# OperacionesLogicasSchmatic.net
KiCad netlist of a schematic drawn in Altium Designer
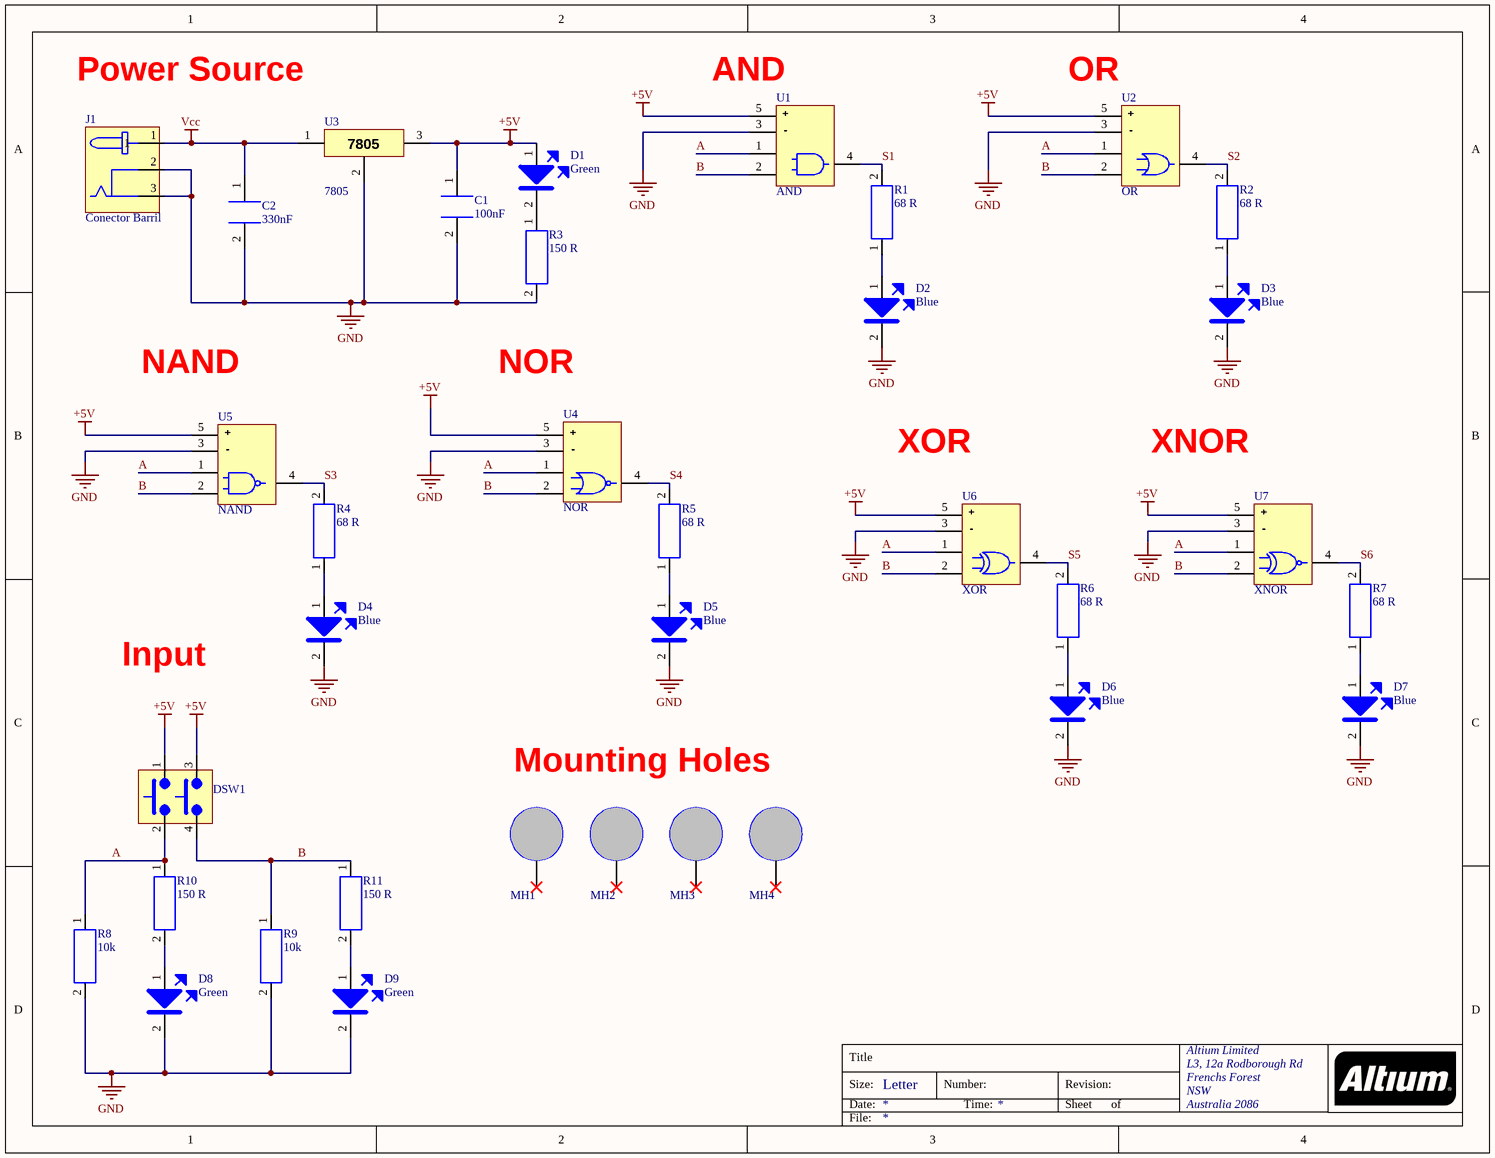
[diagram p0: OperacionesLogicasSchmatic.SchDoc]

(export (version "E")
  (design (tool "Eeschema 10.0.6"))
  (components
    (comp (ref "C1")
      (value "100nF")
      (footprint "Capacitor0805")
      (fields
        (field (name "MANUFACTURER") "KEMET")
        (field (name "MANUFACTURER PART NUMBER") "C0805C104K4RACTU")
        (field (name "TOLERANCE") "10%")
      )
      (libsource (lib "Operaciones_SCH_LIBRARY") (part "C0805C104K4RACTU"))
    )
    (comp (ref "C2")
      (value "330nF")
      (footprint "Capacitor0805")
      (description "CAP CER 0.33UF 16V X7R 0805")
      (fields
        (field (name "MANUFACTURER") "Yageo")
        (field (name "MANUFACTURER PART NUMBER") "CC0805JKX7R7BB334")
      )
      (libsource (lib "Operaciones_SCH_LIBRARY") (part "CC0805JKX7R7BB334"))
    )
    (comp (ref "D1")
      (value "Green")
      (footprint "Led0603")
      (description "LED GREEN CLEAR 0603 SMD")
      (fields
        (field (name "MANUFACTURER") "Vishay Lite-On")
        (field (name "MANUFACTURER PART NUMBER") "LTST-C191GKT")
      )
      (libsource (lib "Operaciones_SCH_LIBRARY") (part "LTST-C191GKT"))
    )
    (comp (ref "D2")
      (value "Blue")
      (footprint "LedTHBlue")
      (description "Standard LEDs - Through Hole 30DG BL NOSTNDOF HI BRT LAMP 470NM 3.2V")
      (fields
        (field (name "MANUFACTURER") "Cree")
        (field (name "MANUFACTURER PART NUMBER") "C503B-BCN-CV0Z0462")
      )
      (libsource (lib "Operaciones_SCH_LIBRARY") (part "C503B-BCN-CV0Z0462"))
    )
    (comp (ref "D3")
      (value "Blue")
      (footprint "LedTHBlue")
      (description "Standard LEDs - Through Hole 30DG BL NOSTNDOF HI BRT LAMP 470NM 3.2V")
      (fields
        (field (name "MANUFACTURER") "Cree")
        (field (name "MANUFACTURER PART NUMBER") "C503B-BCN-CV0Z0462")
      )
      (libsource (lib "Operaciones_SCH_LIBRARY") (part "C503B-BCN-CV0Z0462"))
    )
    (comp (ref "D4")
      (value "Blue")
      (footprint "LedTHBlue")
      (description "Standard LEDs - Through Hole 30DG BL NOSTNDOF HI BRT LAMP 470NM 3.2V")
      (fields
        (field (name "MANUFACTURER") "Cree")
        (field (name "MANUFACTURER PART NUMBER") "C503B-BCN-CV0Z0462")
      )
      (libsource (lib "Operaciones_SCH_LIBRARY") (part "C503B-BCN-CV0Z0462"))
    )
    (comp (ref "D5")
      (value "Blue")
      (footprint "LedTHBlue")
      (description "Standard LEDs - Through Hole 30DG BL NOSTNDOF HI BRT LAMP 470NM 3.2V")
      (fields
        (field (name "MANUFACTURER") "Cree")
        (field (name "MANUFACTURER PART NUMBER") "C503B-BCN-CV0Z0462")
      )
      (libsource (lib "Operaciones_SCH_LIBRARY") (part "C503B-BCN-CV0Z0462"))
    )
    (comp (ref "D6")
      (value "Blue")
      (footprint "LedTHBlue")
      (description "Standard LEDs - Through Hole 30DG BL NOSTNDOF HI BRT LAMP 470NM 3.2V")
      (fields
        (field (name "MANUFACTURER") "Cree")
        (field (name "MANUFACTURER PART NUMBER") "C503B-BCN-CV0Z0462")
      )
      (libsource (lib "Operaciones_SCH_LIBRARY") (part "C503B-BCN-CV0Z0462"))
    )
    (comp (ref "D7")
      (value "Blue")
      (footprint "LedTHBlue")
      (description "Standard LEDs - Through Hole 30DG BL NOSTNDOF HI BRT LAMP 470NM 3.2V")
      (fields
        (field (name "MANUFACTURER") "Cree")
        (field (name "MANUFACTURER PART NUMBER") "C503B-BCN-CV0Z0462")
      )
      (libsource (lib "Operaciones_SCH_LIBRARY") (part "C503B-BCN-CV0Z0462"))
    )
    (comp (ref "D8")
      (value "Green")
      (footprint "LedTHGreen")
      (description "LED RED CLEAR 5MM OVAL T/H")
      (fields
        (field (name "MANUFACTURER") "Cree")
        (field (name "MANUFACTURER PART NUMBER") "C5SMF-RJF-CT0W0BB1")
      )
      (libsource (lib "Operaciones_SCH_LIBRARY") (part "C5SMF-RJF-CT0W0BB1"))
    )
    (comp (ref "D9")
      (value "Green")
      (footprint "LedTHGreen")
      (description "LED RED CLEAR 5MM OVAL T/H")
      (fields
        (field (name "MANUFACTURER") "Cree")
        (field (name "MANUFACTURER PART NUMBER") "C5SMF-RJF-CT0W0BB1")
      )
      (libsource (lib "Operaciones_SCH_LIBRARY") (part "C5SMF-RJF-CT0W0BB1"))
    )
    (comp (ref "DSW1")
      (value "DIP switch 2 pos")
      (footprint "DipSwitch_1x02")
      (description "Slide Switch,STRAIGHT,DPST,ON-OFF,Number Of Positions:2,PC TAIL Terminal,PCB Hole Count:4")
      (fields (field (name "MANUFACTURER") "Omron") (field (name "MANUFACTURER PART NUMBER") "A6T-2104"))
      (libsource (lib "Operaciones_SCH_LIBRARY") (part "A6T-2104"))
    )
    (comp (ref "J1")
      (value "Conector Barril")
      (footprint "JackConector")
      (description "Conn Power PIN 2 POS Solder RA Thru-Hole 3 Terminal 1 Port")
      (fields (field (name "MANUFACTURER") "Kycon") (field (name "MANUFACTURER PART NUMBER") "KLDX-0202-A"))
      (libsource (lib "Operaciones_SCH_LIBRARY") (part "KLDX-0202-A"))
    )
    (comp (ref "MH1")
      (value "Mounting Hole")
      (footprint "MH")
      (libsource (lib "Operaciones_SCH_LIBRARY") (part "MountingHole"))
    )
    (comp (ref "MH2")
      (value "Mounting Hole")
      (footprint "MH")
      (libsource (lib "Operaciones_SCH_LIBRARY") (part "MountingHole"))
    )
    (comp (ref "MH3")
      (value "Mounting Hole")
      (footprint "MH")
      (libsource (lib "Operaciones_SCH_LIBRARY") (part "MountingHole"))
    )
    (comp (ref "MH4")
      (value "Mounting Hole")
      (footprint "MH")
      (libsource (lib "Operaciones_SCH_LIBRARY") (part "MountingHole"))
    )
    (comp (ref "R1")
      (value "68 R")
      (footprint "Resistor0805")
      (description "RES SMD 68 OHM 0.1% 1/4W 1206")
      (fields
        (field (name "MANUFACTURER") "Panasonic")
        (field (name "MANUFACTURER PART NUMBER") "ERA-8AEB680V")
      )
      (libsource (lib "Operaciones_SCH_LIBRARY") (part "ERA-8AEB680V"))
    )
    (comp (ref "R2")
      (value "68 R")
      (footprint "Resistor0805")
      (description "RES SMD 68 OHM 0.1% 1/4W 1206")
      (fields
        (field (name "MANUFACTURER") "Panasonic")
        (field (name "MANUFACTURER PART NUMBER") "ERA-8AEB680V")
      )
      (libsource (lib "Operaciones_SCH_LIBRARY") (part "ERA-8AEB680V"))
    )
    (comp (ref "R3")
      (value "150 R")
      (footprint "Resistor0805")
      (fields
        (field (name "MANUFACTURER") "Yageo")
        (field (name "MANUFACTURER PART NUMBER") "RC0805JR-07150RL")
        (field (name "TOLERANCE") "5%")
      )
      (libsource (lib "Operaciones_SCH_LIBRARY") (part "RC0805JR-07150RL (2)"))
    )
    (comp (ref "R4")
      (value "68 R")
      (footprint "Resistor0805")
      (description "RES SMD 68 OHM 0.1% 1/4W 1206")
      (fields
        (field (name "MANUFACTURER") "Panasonic")
        (field (name "MANUFACTURER PART NUMBER") "ERA-8AEB680V")
      )
      (libsource (lib "Operaciones_SCH_LIBRARY") (part "ERA-8AEB680V"))
    )
    (comp (ref "R5")
      (value "68 R")
      (footprint "Resistor0805")
      (description "RES SMD 68 OHM 0.1% 1/4W 1206")
      (fields
        (field (name "MANUFACTURER") "Panasonic")
        (field (name "MANUFACTURER PART NUMBER") "ERA-8AEB680V")
      )
      (libsource (lib "Operaciones_SCH_LIBRARY") (part "ERA-8AEB680V"))
    )
    (comp (ref "R6")
      (value "68 R")
      (footprint "Resistor0805")
      (description "RES SMD 68 OHM 0.1% 1/4W 1206")
      (fields
        (field (name "MANUFACTURER") "Panasonic")
        (field (name "MANUFACTURER PART NUMBER") "ERA-8AEB680V")
      )
      (libsource (lib "Operaciones_SCH_LIBRARY") (part "ERA-8AEB680V"))
    )
    (comp (ref "R7")
      (value "68 R")
      (footprint "Resistor0805")
      (description "RES SMD 68 OHM 0.1% 1/4W 1206")
      (fields
        (field (name "MANUFACTURER") "Panasonic")
        (field (name "MANUFACTURER PART NUMBER") "ERA-8AEB680V")
      )
      (libsource (lib "Operaciones_SCH_LIBRARY") (part "ERA-8AEB680V"))
    )
    (comp (ref "R8")
      (value "10k")
      (footprint "Resistor0805")
      (description "RES 10K OHM 1% 1/4W 0805")
      (fields
        (field (name "MANUFACTURER") "Stackpole Electronics")
        (field (name "MANUFACTURER PART NUMBER") "RNCP0805FTD10K0")
      )
      (libsource (lib "Operaciones_SCH_LIBRARY") (part "RNCP0805FTD10K0"))
    )
    (comp (ref "R9")
      (value "10k")
      (footprint "Resistor0805")
      (description "RES 10K OHM 1% 1/4W 0805")
      (fields
        (field (name "MANUFACTURER") "Stackpole Electronics")
        (field (name "MANUFACTURER PART NUMBER") "RNCP0805FTD10K0")
      )
      (libsource (lib "Operaciones_SCH_LIBRARY") (part "RNCP0805FTD10K0"))
    )
    (comp (ref "R10")
      (value "150 R")
      (footprint "Resistor0805")
      (fields
        (field (name "MANUFACTURER") "Yageo")
        (field (name "MANUFACTURER PART NUMBER") "RC0805JR-07150RL")
        (field (name "TOLERANCE") "5%")
      )
      (libsource (lib "Operaciones_SCH_LIBRARY") (part "RC0805JR-07150RL (2)"))
    )
    (comp (ref "R11")
      (value "150 R")
      (footprint "Resistor0805")
      (fields
        (field (name "MANUFACTURER") "Yageo")
        (field (name "MANUFACTURER PART NUMBER") "RC0805JR-07150RL")
        (field (name "TOLERANCE") "5%")
      )
      (libsource (lib "Operaciones_SCH_LIBRARY") (part "RC0805JR-07150RL (2)"))
    )
    (comp (ref "U1")
      (value "AND")
      (footprint "DCK_SC_70_5")
      (description "IC GATE AND 1CH 2-INP SC70-5")
      (fields
        (field (name "MANUFACTURER") "Texas Instruments")
        (field (name "MANUFACTURER PART NUMBER") "SN74AHCT1G08DCKR")
      )
      (libsource (lib "Operaciones_SCH_LIBRARY") (part "SN74AHCT1G08DCKR"))
    )
    (comp (ref "U2")
      (value "OR")
      (footprint "DCK_SC_70_5")
      (description "IC GATE OR 1CH 2-INP SC70-5")
      (fields
        (field (name "MANUFACTURER") "Texas Instruments")
        (field (name "MANUFACTURER PART NUMBER") "SN74LVC1G32DCKR")
      )
      (libsource (lib "Operaciones_SCH_LIBRARY") (part "SN74LVC1G32DCKR"))
    )
    (comp (ref "U3")
      (value "7805")
      (footprint "T0-236")
      (description "LDO Regulator Pos 5V 1.5A 4-Pin(3+Tab) TO-263 T/R")
      (fields
        (field (name "MANUFACTURER") "Texas Instruments")
        (field (name "MANUFACTURER PART NUMBER") "UA7805CKTTR")
      )
      (libsource (lib "Operaciones_SCH_LIBRARY") (part "UA7805CKTTR"))
    )
    (comp (ref "U4")
      (value "NOR")
      (footprint "DCK_SC_70_5")
      (description "Enhanced Product Single 2-Input Positive-Nor Gate 5-SC70 -55 to 125")
      (fields
        (field (name "MANUFACTURER") "Texas Instruments")
        (field (name "MANUFACTURER PART NUMBER") "SN74LVC1G02MDCKREP")
      )
      (libsource (lib "Operaciones_SCH_LIBRARY") (part "SN74LVC1G02MDCKREP"))
    )
    (comp (ref "U5")
      (value "NAND")
      (footprint "DCK_SC_70_5")
      (fields
        (field (name "MANUFACTURER") "Texas Instruments")
        (field (name "MANUFACTURER PART NUMBER") "SN74LVC1G00DCKR")
      )
      (libsource (lib "Operaciones_SCH_LIBRARY") (part "SN74LVC1G00DCKR"))
    )
    (comp (ref "U6")
      (value "XOR")
      (footprint "DCK_SC_70_5")
      (fields
        (field (name "MANUFACTURER") "Texas Instruments")
        (field (name "MANUFACTURER PART NUMBER") "SN74LVC1G86DCKR")
      )
      (libsource (lib "Operaciones_SCH_LIBRARY") (part "SN74LVC1G86DCKR"))
    )
    (comp (ref "U7")
      (value "XNOR")
      (footprint "DCK_SC_70_5")
      (description "TEXAS INSTRUMENTS - SN74AUP1T87DCKR - LOGIC, XNOR GATE, SINGLE, SC-70-5")
      (fields
        (field (name "MANUFACTURER") "Texas Instruments")
        (field (name "MANUFACTURER PART NUMBER") "SN74AUP1T87DCKR")
      )
      (libsource (lib "Operaciones_SCH_LIBRARY") (part "SN74AUP1T87DCKR"))
    )
  )
  (nets
    (net (code "1") (name "+5V") (class "Default")
      (node (ref "C1") (pin "1") (pinfunction "1_1") (pintype "passive"))
      (node (ref "D1") (pin "1") (pinfunction "A_1") (pintype "passive"))
      (node (ref "DSW1") (pin "1") (pinfunction "1_1") (pintype "passive"))
      (node (ref "DSW1") (pin "3") (pinfunction "3_3") (pintype "passive"))
      (node (ref "U1") (pin "5") (pinfunction "VCC_5") (pintype "passive"))
      (node (ref "U2") (pin "5") (pinfunction "VCC_5") (pintype "passive"))
      (node (ref "U3") (pin "3") (pinfunction "3_3") (pintype "passive"))
      (node (ref "U4") (pin "5") (pinfunction "VCC_5") (pintype "passive"))
      (node (ref "U5") (pin "5") (pinfunction "VCC_5") (pintype "passive"))
      (node (ref "U6") (pin "5") (pinfunction "VCC_5") (pintype "passive"))
      (node (ref "U7") (pin "5") (pinfunction "VCC_5") (pintype "passive"))
    )
    (net (code "2") (name "/A") (class "Default")
      (node (ref "DSW1") (pin "2") (pinfunction "2_2") (pintype "passive"))
      (node (ref "R10") (pin "1") (pinfunction "1_1") (pintype "passive"))
      (node (ref "R8") (pin "1") (pinfunction "1_1") (pintype "passive"))
      (node (ref "U1") (pin "1") (pinfunction "A_1") (pintype "passive"))
      (node (ref "U2") (pin "1") (pinfunction "A_1") (pintype "passive"))
      (node (ref "U4") (pin "1") (pinfunction "A_1") (pintype "passive"))
      (node (ref "U5") (pin "1") (pinfunction "A_1") (pintype "passive"))
      (node (ref "U6") (pin "1") (pinfunction "A_1") (pintype "passive"))
      (node (ref "U7") (pin "1") (pinfunction "A_1") (pintype "passive"))
    )
    (net (code "3") (name "/B") (class "Default")
      (node (ref "DSW1") (pin "4") (pinfunction "4_4") (pintype "passive"))
      (node (ref "R11") (pin "1") (pinfunction "1_1") (pintype "passive"))
      (node (ref "R9") (pin "1") (pinfunction "1_1") (pintype "passive"))
      (node (ref "U1") (pin "2") (pinfunction "B_2") (pintype "passive"))
      (node (ref "U2") (pin "2") (pinfunction "B_2") (pintype "passive"))
      (node (ref "U4") (pin "2") (pinfunction "B_2") (pintype "passive"))
      (node (ref "U5") (pin "2") (pinfunction "B_2") (pintype "passive"))
      (node (ref "U6") (pin "2") (pinfunction "B_2") (pintype "passive"))
      (node (ref "U7") (pin "2") (pinfunction "B_2") (pintype "passive"))
    )
    (net (code "4") (name "/S1") (class "Default")
      (node (ref "R1") (pin "2") (pinfunction "2_2") (pintype "passive"))
      (node (ref "U1") (pin "4") (pinfunction "Y_4") (pintype "passive"))
    )
    (net (code "5") (name "/S2") (class "Default")
      (node (ref "R2") (pin "2") (pinfunction "2_2") (pintype "passive"))
      (node (ref "U2") (pin "4") (pinfunction "Y_4") (pintype "passive"))
    )
    (net (code "6") (name "/S3") (class "Default")
      (node (ref "R4") (pin "2") (pinfunction "2_2") (pintype "passive"))
      (node (ref "U5") (pin "4") (pinfunction "Y_4") (pintype "passive"))
    )
    (net (code "7") (name "/S4") (class "Default")
      (node (ref "R5") (pin "2") (pinfunction "2_2") (pintype "passive"))
      (node (ref "U4") (pin "4") (pinfunction "Y_4") (pintype "passive"))
    )
    (net (code "8") (name "/S5") (class "Default")
      (node (ref "R6") (pin "2") (pinfunction "2_2") (pintype "passive"))
      (node (ref "U6") (pin "4") (pinfunction "Y_4") (pintype "passive"))
    )
    (net (code "9") (name "/S6") (class "Default")
      (node (ref "R7") (pin "2") (pinfunction "2_2") (pintype "passive"))
      (node (ref "U7") (pin "4") (pinfunction "Y_4") (pintype "passive"))
    )
    (net (code "10") (name "GND") (class "Default")
      (node (ref "C1") (pin "2") (pinfunction "2_2") (pintype "passive"))
      (node (ref "C2") (pin "2") (pinfunction "2_2") (pintype "passive"))
      (node (ref "D2") (pin "2") (pinfunction "C_2") (pintype "passive"))
      (node (ref "D3") (pin "2") (pinfunction "C_2") (pintype "passive"))
      (node (ref "D4") (pin "2") (pinfunction "C_2") (pintype "passive"))
      (node (ref "D5") (pin "2") (pinfunction "C_2") (pintype "passive"))
      (node (ref "D6") (pin "2") (pinfunction "C_2") (pintype "passive"))
      (node (ref "D7") (pin "2") (pinfunction "C_2") (pintype "passive"))
      (node (ref "D8") (pin "2") (pinfunction "C_2") (pintype "passive"))
      (node (ref "D9") (pin "2") (pinfunction "C_2") (pintype "passive"))
      (node (ref "J1") (pin "2") (pinfunction "2_2") (pintype "passive"))
      (node (ref "J1") (pin "3") (pinfunction "3_3") (pintype "passive"))
      (node (ref "R3") (pin "2") (pinfunction "2_2") (pintype "passive"))
      (node (ref "R8") (pin "2") (pinfunction "2_2") (pintype "passive"))
      (node (ref "R9") (pin "2") (pinfunction "2_2") (pintype "passive"))
      (node (ref "U1") (pin "3") (pinfunction "GND_3") (pintype "passive"))
      (node (ref "U2") (pin "3") (pinfunction "GND_3") (pintype "passive"))
      (node (ref "U3") (pin "2") (pinfunction "2_2") (pintype "passive"))
      (node (ref "U4") (pin "3") (pinfunction "GND_3") (pintype "passive"))
      (node (ref "U5") (pin "3") (pinfunction "GND_3") (pintype "passive"))
      (node (ref "U6") (pin "3") (pinfunction "GND_3") (pintype "passive"))
      (node (ref "U7") (pin "3") (pinfunction "GND_3") (pintype "passive"))
    )
    (net (code "11") (name "Net-(D1-C)") (class "Default")
      (node (ref "D1") (pin "2") (pinfunction "C_2") (pintype "passive"))
      (node (ref "R3") (pin "1") (pinfunction "1_1") (pintype "passive"))
    )
    (net (code "12") (name "Net-(D2-A)") (class "Default")
      (node (ref "D2") (pin "1") (pinfunction "A_1") (pintype "passive"))
      (node (ref "R1") (pin "1") (pinfunction "1_1") (pintype "passive"))
    )
    (net (code "13") (name "Net-(D3-A)") (class "Default")
      (node (ref "D3") (pin "1") (pinfunction "A_1") (pintype "passive"))
      (node (ref "R2") (pin "1") (pinfunction "1_1") (pintype "passive"))
    )
    (net (code "14") (name "Net-(D4-A)") (class "Default")
      (node (ref "D4") (pin "1") (pinfunction "A_1") (pintype "passive"))
      (node (ref "R4") (pin "1") (pinfunction "1_1") (pintype "passive"))
    )
    (net (code "15") (name "Net-(D5-A)") (class "Default")
      (node (ref "D5") (pin "1") (pinfunction "A_1") (pintype "passive"))
      (node (ref "R5") (pin "1") (pinfunction "1_1") (pintype "passive"))
    )
    (net (code "16") (name "Net-(D6-A)") (class "Default")
      (node (ref "D6") (pin "1") (pinfunction "A_1") (pintype "passive"))
      (node (ref "R6") (pin "1") (pinfunction "1_1") (pintype "passive"))
    )
    (net (code "17") (name "Net-(D7-A)") (class "Default")
      (node (ref "D7") (pin "1") (pinfunction "A_1") (pintype "passive"))
      (node (ref "R7") (pin "1") (pinfunction "1_1") (pintype "passive"))
    )
    (net (code "18") (name "Net-(D8-A)") (class "Default")
      (node (ref "D8") (pin "1") (pinfunction "A_1") (pintype "passive"))
      (node (ref "R10") (pin "2") (pinfunction "2_2") (pintype "passive"))
    )
    (net (code "19") (name "Net-(D9-A)") (class "Default")
      (node (ref "D9") (pin "1") (pinfunction "A_1") (pintype "passive"))
      (node (ref "R11") (pin "2") (pinfunction "2_2") (pintype "passive"))
    )
    (net (code "20") (name "Vcc") (class "Default")
      (node (ref "C2") (pin "1") (pinfunction "1_1") (pintype "passive"))
      (node (ref "J1") (pin "1") (pinfunction "1_1") (pintype "passive"))
      (node (ref "U3") (pin "1") (pinfunction "1_1") (pintype "passive"))
    )
    (net (code "21") (name "unconnected-(MH1-Pad1)") (class "Default")
      (node (ref "MH1") (pin "1") (pinfunction "1_1") (pintype "passive+no_connect"))
    )
    (net (code "22") (name "unconnected-(MH2-Pad1)") (class "Default")
      (node (ref "MH2") (pin "1") (pinfunction "1_1") (pintype "passive+no_connect"))
    )
    (net (code "23") (name "unconnected-(MH3-Pad1)") (class "Default")
      (node (ref "MH3") (pin "1") (pinfunction "1_1") (pintype "passive+no_connect"))
    )
    (net (code "24") (name "unconnected-(MH4-Pad1)") (class "Default")
      (node (ref "MH4") (pin "1") (pinfunction "1_1") (pintype "passive+no_connect"))
    )
  )
)
